# motor_surucu.net
KiCad netlist of a schematic drawn in Altium Designer
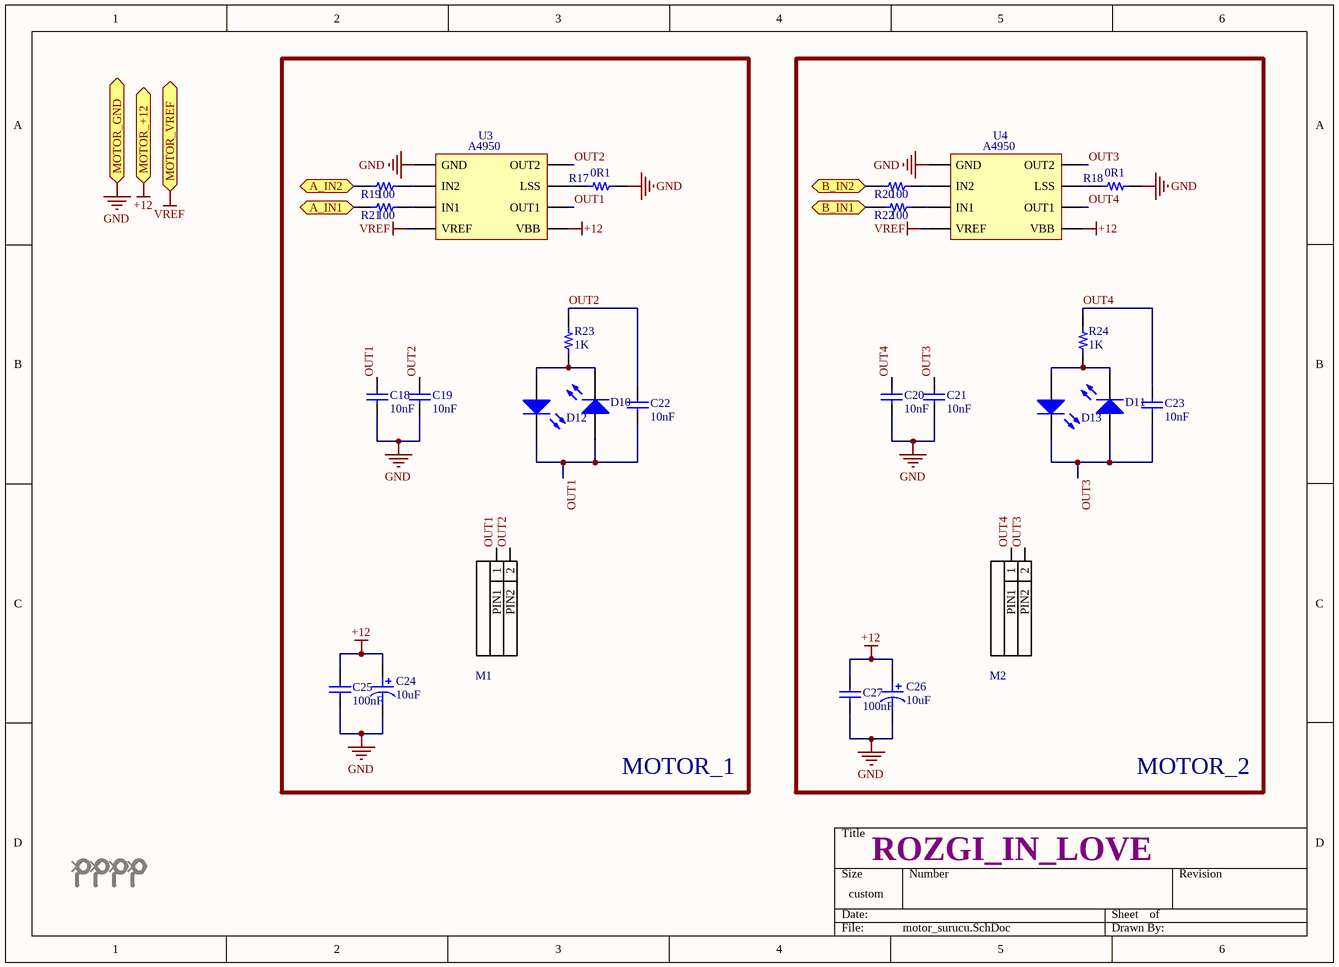
[diagram p0: motor_surucu.SchDoc]

(export (version "E")
  (design (tool "Eeschema 10.0.6"))
  (components
    (comp (ref "1") (value "VİDA") (footprint "M2") (libsource (lib "genel") (part "VİDA")))
    (comp (ref "2") (value "VİDA") (footprint "M2") (libsource (lib "genel") (part "VİDA")))
    (comp (ref "3") (value "VİDA") (footprint "M2") (libsource (lib "genel") (part "VİDA")))
    (comp (ref "4") (value "VİDA") (footprint "M2") (libsource (lib "genel") (part "VİDA")))
    (comp (ref "C18")
      (value "10nF")
      (footprint "CAP SMD C0603")
      (description "CAP SMD")
      (libsource (lib "genel") (part "CAP SMD THT"))
    )
    (comp (ref "C19")
      (value "10nF")
      (footprint "CAP SMD C0603")
      (description "CAP SMD")
      (libsource (lib "genel") (part "CAP SMD THT"))
    )
    (comp (ref "C20")
      (value "10nF")
      (footprint "CAP SMD C0603")
      (description "CAP SMD")
      (libsource (lib "genel") (part "CAP SMD THT"))
    )
    (comp (ref "C21")
      (value "10nF")
      (footprint "CAP SMD C0603")
      (description "CAP SMD")
      (libsource (lib "genel") (part "CAP SMD THT"))
    )
    (comp (ref "C22")
      (value "10nF")
      (footprint "CAP SMD C0603")
      (description "CAP SMD")
      (libsource (lib "genel") (part "CAP SMD THT"))
    )
    (comp (ref "C23")
      (value "10nF")
      (footprint "CAP SMD C0603")
      (description "CAP SMD")
      (libsource (lib "genel") (part "CAP SMD THT"))
    )
    (comp (ref "C24")
      (value "10uF")
      (footprint "Cap Tantal 3528 - Type B")
      (description "CAP-TANTAL")
      (libsource (lib "genel") (part "CAP-SMD -TANTAL"))
    )
    (comp (ref "C25")
      (value "100nF")
      (footprint "CAP SMD C0603")
      (description "CAP SMD")
      (libsource (lib "genel") (part "CAP SMD THT"))
    )
    (comp (ref "C26")
      (value "10uF")
      (footprint "Cap Tantal 3528 - Type B")
      (description "CAP-TANTAL")
      (libsource (lib "genel") (part "CAP-SMD -TANTAL"))
    )
    (comp (ref "C27")
      (value "100nF")
      (footprint "CAP SMD C0603")
      (description "CAP SMD")
      (libsource (lib "genel") (part "CAP SMD THT"))
    )
    (comp (ref "D10")
      (value "~")
      (footprint "LED 0603/1608 GREEN")
      (description "Typical LED")
      (fields (field (name "VOLTAGE") "3V"))
      (libsource (lib "genel") (part "LED"))
    )
    (comp (ref "D11")
      (value "~")
      (footprint "LED 0603/1608 GREEN")
      (description "Typical LED")
      (fields (field (name "VOLTAGE") "3V"))
      (libsource (lib "genel") (part "LED"))
    )
    (comp (ref "D12")
      (value "~")
      (footprint "LED 0603/1608 RED")
      (description "Typical LED")
      (fields (field (name "VOLTAGE") "3V"))
      (libsource (lib "genel") (part "LED"))
    )
    (comp (ref "D13")
      (value "~")
      (footprint "LED 0603/1608 RED")
      (description "Typical LED")
      (fields (field (name "VOLTAGE") "3V"))
      (libsource (lib "genel") (part "LED"))
    )
    (comp (ref "M1")
      (value "Ğàçú¸ì PLS-2")
      (footprint "HDR1X2")
      (description "Male, 2 pin single in line, 2.54")
      (libsource (lib "header") (part "HDR 1x2"))
    )
    (comp (ref "M2")
      (value "Ğàçú¸ì PLS-2")
      (footprint "HDR1X2")
      (description "Male, 2 pin single in line, 2.54")
      (libsource (lib "header") (part "HDR 1x2"))
    )
    (comp (ref "R17")
      (value "0R1")
      (footprint "STACKPOLE CSRN2512")
      (description "RES")
      (libsource (lib "genel") (part "RES"))
    )
    (comp (ref "R18")
      (value "0R1")
      (footprint "STACKPOLE CSRN2512")
      (description "RES")
      (libsource (lib "genel") (part "RES"))
    )
    (comp (ref "R19")
      (value "100")
      (footprint "RES 0603")
      (description "RES")
      (libsource (lib "genel") (part "RES"))
    )
    (comp (ref "R20")
      (value "100")
      (footprint "RES 0603")
      (description "RES")
      (libsource (lib "genel") (part "RES"))
    )
    (comp (ref "R21")
      (value "100")
      (footprint "RES 0603")
      (description "RES")
      (libsource (lib "genel") (part "RES"))
    )
    (comp (ref "R22")
      (value "100")
      (footprint "RES 0603")
      (description "RES")
      (libsource (lib "genel") (part "RES"))
    )
    (comp (ref "R23")
      (value "1K")
      (footprint "RES 0603")
      (description "RES")
      (libsource (lib "genel") (part "RES"))
    )
    (comp (ref "R24")
      (value "1K")
      (footprint "RES 0603")
      (description "RES")
      (libsource (lib "genel") (part "RES"))
    )
    (comp (ref "U3") (value "A4950") (footprint "SOIC8-EP_motor") (libsource (lib "genel") (part "A4950")))
    (comp (ref "U4") (value "A4950") (footprint "SOIC8-EP_motor") (libsource (lib "genel") (part "A4950")))
  )
  (nets
    (net (code "1") (name "+12") (class "Default")
      (node (ref "C24") (pin "1") (pinfunction "1_1") (pintype "passive"))
      (node (ref "C25") (pin "2") (pinfunction "2_2") (pintype "passive"))
      (node (ref "C26") (pin "1") (pinfunction "1_1") (pintype "passive"))
      (node (ref "C27") (pin "2") (pinfunction "2_2") (pintype "passive"))
      (node (ref "U3") (pin "5") (pinfunction "VBB_5") (pintype "passive"))
      (node (ref "U4") (pin "5") (pinfunction "VBB_5") (pintype "passive"))
    )
    (net (code "2") (name "/A_IN1") (class "Default")
      (node (ref "R21") (pin "1") (pinfunction "1_1") (pintype "passive"))
    )
    (net (code "3") (name "/A_IN2") (class "Default")
      (node (ref "R19") (pin "1") (pinfunction "1_1") (pintype "passive"))
    )
    (net (code "4") (name "/B_IN1") (class "Default")
      (node (ref "R22") (pin "1") (pinfunction "1_1") (pintype "passive"))
    )
    (net (code "5") (name "/B_IN2") (class "Default")
      (node (ref "R20") (pin "1") (pinfunction "1_1") (pintype "passive"))
    )
    (net (code "6") (name "/OUT1") (class "Default")
      (node (ref "C18") (pin "2") (pinfunction "2_2") (pintype "passive"))
      (node (ref "C22") (pin "1") (pinfunction "1_1") (pintype "passive"))
      (node (ref "D10") (pin "2") (pinfunction "A_2") (pintype "passive"))
      (node (ref "D12") (pin "1") (pinfunction "C_1") (pintype "passive"))
      (node (ref "M1") (pin "1") (pinfunction "PIN1_1") (pintype "passive"))
      (node (ref "U3") (pin "6") (pinfunction "OUT1_6") (pintype "passive"))
    )
    (net (code "7") (name "/OUT2") (class "Default")
      (node (ref "C19") (pin "2") (pinfunction "2_2") (pintype "passive"))
      (node (ref "C22") (pin "2") (pinfunction "2_2") (pintype "passive"))
      (node (ref "M1") (pin "2") (pinfunction "PIN2_2") (pintype "passive"))
      (node (ref "R23") (pin "2") (pinfunction "2_2") (pintype "passive"))
      (node (ref "U3") (pin "8") (pinfunction "OUT2_8") (pintype "passive"))
    )
    (net (code "8") (name "/OUT3") (class "Default")
      (node (ref "C21") (pin "2") (pinfunction "2_2") (pintype "passive"))
      (node (ref "C23") (pin "1") (pinfunction "1_1") (pintype "passive"))
      (node (ref "D11") (pin "2") (pinfunction "A_2") (pintype "passive"))
      (node (ref "D13") (pin "1") (pinfunction "C_1") (pintype "passive"))
      (node (ref "M2") (pin "2") (pinfunction "PIN2_2") (pintype "passive"))
      (node (ref "U4") (pin "8") (pinfunction "OUT2_8") (pintype "passive"))
    )
    (net (code "9") (name "/OUT4") (class "Default")
      (node (ref "C20") (pin "2") (pinfunction "2_2") (pintype "passive"))
      (node (ref "C23") (pin "2") (pinfunction "2_2") (pintype "passive"))
      (node (ref "M2") (pin "1") (pinfunction "PIN1_1") (pintype "passive"))
      (node (ref "R24") (pin "2") (pinfunction "2_2") (pintype "passive"))
      (node (ref "U4") (pin "6") (pinfunction "OUT1_6") (pintype "passive"))
    )
    (net (code "10") (name "GND") (class "Default")
      (node (ref "C18") (pin "1") (pinfunction "1_1") (pintype "passive"))
      (node (ref "C19") (pin "1") (pinfunction "1_1") (pintype "passive"))
      (node (ref "C20") (pin "1") (pinfunction "1_1") (pintype "passive"))
      (node (ref "C21") (pin "1") (pinfunction "1_1") (pintype "passive"))
      (node (ref "C24") (pin "2") (pinfunction "2_2") (pintype "passive"))
      (node (ref "C25") (pin "1") (pinfunction "1_1") (pintype "passive"))
      (node (ref "C26") (pin "2") (pinfunction "2_2") (pintype "passive"))
      (node (ref "C27") (pin "1") (pinfunction "1_1") (pintype "passive"))
      (node (ref "R17") (pin "2") (pinfunction "2_2") (pintype "passive"))
      (node (ref "R18") (pin "2") (pinfunction "2_2") (pintype "passive"))
      (node (ref "U3") (pin "1") (pinfunction "GND_1") (pintype "passive"))
      (node (ref "U4") (pin "1") (pinfunction "GND_1") (pintype "passive"))
    )
    (net (code "11") (name "Net-(D10-C)") (class "Default")
      (node (ref "D10") (pin "1") (pinfunction "C_1") (pintype "passive"))
      (node (ref "D12") (pin "2") (pinfunction "A_2") (pintype "passive"))
      (node (ref "R23") (pin "1") (pinfunction "1_1") (pintype "passive"))
    )
    (net (code "12") (name "Net-(D11-C)") (class "Default")
      (node (ref "D11") (pin "1") (pinfunction "C_1") (pintype "passive"))
      (node (ref "D13") (pin "2") (pinfunction "A_2") (pintype "passive"))
      (node (ref "R24") (pin "1") (pinfunction "1_1") (pintype "passive"))
    )
    (net (code "13") (name "Net-(U3-IN1)") (class "Default")
      (node (ref "R21") (pin "2") (pinfunction "2_2") (pintype "passive"))
      (node (ref "U3") (pin "3") (pinfunction "IN1_3") (pintype "passive"))
    )
    (net (code "14") (name "Net-(U3-IN2)") (class "Default")
      (node (ref "R19") (pin "2") (pinfunction "2_2") (pintype "passive"))
      (node (ref "U3") (pin "2") (pinfunction "IN2_2") (pintype "passive"))
    )
    (net (code "15") (name "Net-(U3-LSS)") (class "Default")
      (node (ref "R17") (pin "1") (pinfunction "1_1") (pintype "passive"))
      (node (ref "U3") (pin "7") (pinfunction "LSS_7") (pintype "passive"))
    )
    (net (code "16") (name "Net-(U4-IN1)") (class "Default")
      (node (ref "R22") (pin "2") (pinfunction "2_2") (pintype "passive"))
      (node (ref "U4") (pin "3") (pinfunction "IN1_3") (pintype "passive"))
    )
    (net (code "17") (name "Net-(U4-IN2)") (class "Default")
      (node (ref "R20") (pin "2") (pinfunction "2_2") (pintype "passive"))
      (node (ref "U4") (pin "2") (pinfunction "IN2_2") (pintype "passive"))
    )
    (net (code "18") (name "Net-(U4-LSS)") (class "Default")
      (node (ref "R18") (pin "1") (pinfunction "1_1") (pintype "passive"))
      (node (ref "U4") (pin "7") (pinfunction "LSS_7") (pintype "passive"))
    )
    (net (code "19") (name "VREF") (class "Default")
      (node (ref "U3") (pin "4") (pinfunction "VREF_4") (pintype "passive"))
      (node (ref "U4") (pin "4") (pinfunction "VREF_4") (pintype "passive"))
    )
  )
)
